# Management_of_Charging_Discharging_Tri-a.net
KiCad netlist of a schematic drawn in Altium Designer
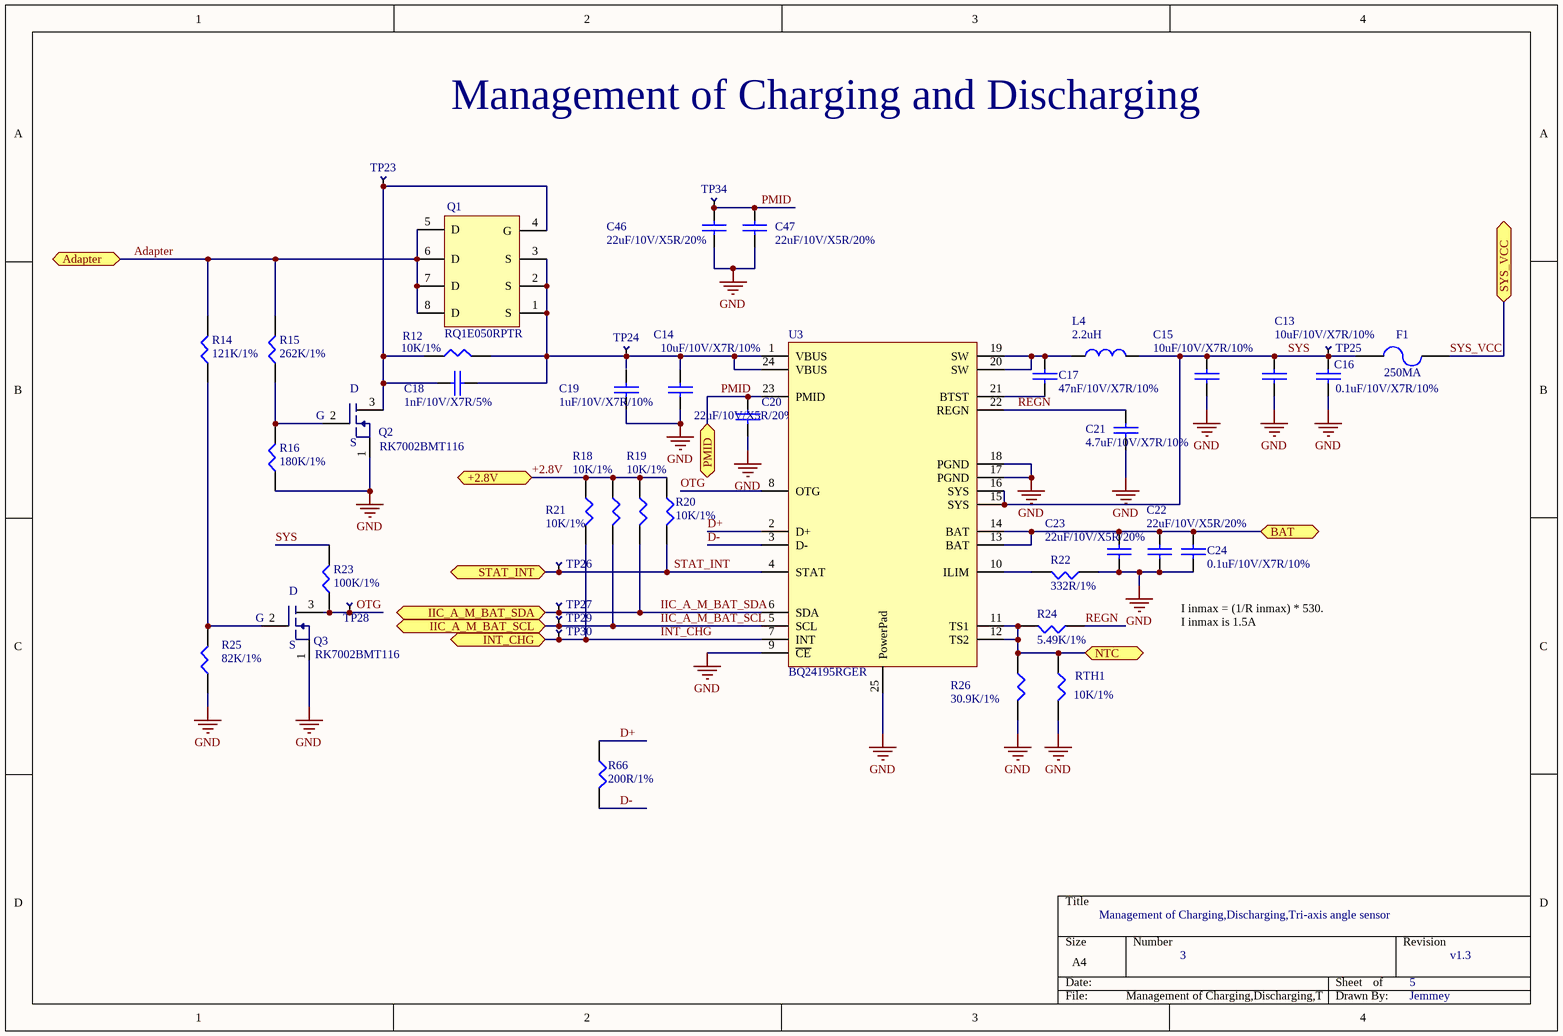
[diagram p0: Management of Charging,Discharging,Tri-axis angle sensor.SchDoc]

(export (version "E")
  (design (tool "Eeschema 10.0.6"))
  (components
    (comp (ref "C13")
      (value "10uF/10V/X7R/10%")
      (footprint "0603C")
      (description "厂家：Murata，型号：GRM188R61A106KE69D")
      (libsource (lib "*") (part "CAP"))
    )
    (comp (ref "C14")
      (value "10uF/10V/X7R/10%")
      (footprint "0603C")
      (description "厂家：Murata，型号：GRM188R61A106KE69D")
      (libsource (lib "*") (part "CAP"))
    )
    (comp (ref "C15")
      (value "10uF/10V/X7R/10%")
      (footprint "0603C")
      (description "厂家：Murata，型号：GRM188R61A106KE69D")
      (libsource (lib "*") (part "CAP"))
    )
    (comp (ref "C16")
      (value "0.1uF/10V/X7R/10%")
      (footprint "0402C")
      (description "厂家：Murata，型号：GRM155R71A104KA01D")
      (libsource (lib "*") (part "CAP"))
    )
    (comp (ref "C17")
      (value "47nF/10V/X7R/10%")
      (footprint "0402C")
      (description "厂家：Murata，型号：GRM155R71H473KE14D")
      (libsource (lib "*") (part "CAP"))
    )
    (comp (ref "C18")
      (value "1nF/10V/X7R/5%")
      (footprint "0402C")
      (description "厂家：Murata，型号：GRM1555C1H102JA01D")
      (libsource (lib "*") (part "CAP"))
    )
    (comp (ref "C19")
      (value "1uF/10V/X7R/10%")
      (footprint "0402C")
      (description "厂家：Murata，型号：GRM155R61C105KA12D")
      (libsource (lib "*") (part "CAP"))
    )
    (comp (ref "C20")
      (value "22uF/10V/X5R/20%")
      (footprint "0603C")
      (description "厂家：Murata，型号：GRM188R61A226ME15D")
      (libsource (lib "*") (part "CAP"))
    )
    (comp (ref "C21")
      (value "4.7uF/10V/X7R/10%")
      (footprint "0603C")
      (description "厂家：Murata，型号：GRM188R61A475KE15D")
      (libsource (lib "*") (part "CAP"))
    )
    (comp (ref "C22")
      (value "22uF/10V/X5R/20%")
      (footprint "0603C")
      (description "厂家：Murata，型号：GRM188R61A226ME15D")
      (libsource (lib "*") (part "CAP"))
    )
    (comp (ref "C23")
      (value "22uF/10V/X5R/20%")
      (footprint "0603C")
      (description "厂家：Murata，型号：GRM188R61A226ME15D")
      (libsource (lib "*") (part "CAP"))
    )
    (comp (ref "C24")
      (value "0.1uF/10V/X7R/10%")
      (footprint "0402C")
      (description "厂家：Murata，型号：GRM155R71A104KA01D")
      (libsource (lib "*") (part "CAP"))
    )
    (comp (ref "C46")
      (value "22uF/10V/X5R/20%")
      (footprint "0603C")
      (description "厂家：Murata，型号：GRM188R61A226ME15D")
      (libsource (lib "*") (part "CAP"))
    )
    (comp (ref "C47")
      (value "22uF/10V/X5R/20%")
      (footprint "0603C")
      (description "厂家：Murata，型号：GRM188R61A226ME15D")
      (libsource (lib "*") (part "CAP"))
    )
    (comp (ref "F1")
      (value "250MA")
      (footprint "1206")
      (description "厂家：万瑞和，型号：WH1206-050")
      (libsource (lib "*") (part "FUSE2"))
    )
    (comp (ref "L4")
      (value "2.2uH")
      (footprint "MMD")
      (description "厂家：Mag，型号：MMD-05AHN2R2M-X2-RM")
      (libsource (lib "Amber") (part "CHOKE"))
    )
    (comp (ref "Q1")
      (value "RQ1E050RPTR")
      (footprint "TSMT8")
      (description "厂家：ROHM，型号：   RQ1E050RPTR")
      (libsource (lib "Amber") (part "RQ1E050RP"))
    )
    (comp (ref "Q2")
      (value "RK7002BMT116")
      (footprint "SOT23")
      (description "厂家：Vishay，型号：RK7002BMT116")
      (libsource (lib "Amber") (part "RK7002BMT116"))
    )
    (comp (ref "Q3")
      (value "RK7002BMT116")
      (footprint "SOT23")
      (description "厂家：Vishay，型号：RK7002BMT116")
      (libsource (lib "Amber") (part "RK7002BMT116"))
    )
    (comp (ref "R12")
      (value "10K/1%")
      (footprint "0402R")
      (description "厂家：Yageo，型号：RC0402FR-0710KL")
      (libsource (lib "*") (part "RES1"))
    )
    (comp (ref "R14")
      (value "121K/1%")
      (footprint "0402R")
      (description "厂家：Yageo，型号：RC0402FR-07121KL")
      (libsource (lib "*") (part "RES1"))
    )
    (comp (ref "R15")
      (value "262K/1%")
      (footprint "0402R")
      (description "厂家：Yageo，型号：RC0402FR-07262KL")
      (libsource (lib "*") (part "RES1"))
    )
    (comp (ref "R16")
      (value "180K/1%")
      (footprint "0402R")
      (description "厂家：Yageo，型号：RC0402FR-07180KL")
      (libsource (lib "*") (part "RES1"))
    )
    (comp (ref "R18")
      (value "10K/1%")
      (footprint "0402R")
      (description "厂家：Yageo，型号：RC0402FR-0710KL")
      (libsource (lib "*") (part "RES1"))
    )
    (comp (ref "R19")
      (value "10K/1%")
      (footprint "0402R")
      (description "厂家：Yageo，型号：RC0402FR-0710KL")
      (libsource (lib "*") (part "RES1"))
    )
    (comp (ref "R20")
      (value "10K/1%")
      (footprint "0402R")
      (description "厂家：Yageo，型号：RC0402FR-0710KL")
      (libsource (lib "*") (part "RES1"))
    )
    (comp (ref "R21")
      (value "10K/1%")
      (footprint "0402R")
      (description "厂家：Yageo，型号：RC0402FR-0710KL")
      (libsource (lib "*") (part "RES1"))
    )
    (comp (ref "R22")
      (value "332R/1%")
      (footprint "0402R")
      (description "厂家：Yageo，型号：RC0402FR-07332RL")
      (libsource (lib "*") (part "RES1"))
    )
    (comp (ref "R23")
      (value "100K/1%")
      (footprint "0402R")
      (description "厂家：Yageo，型号：RC0402FR-07100KL")
      (libsource (lib "*") (part "RES1"))
    )
    (comp (ref "R24")
      (value "5.49K/1%")
      (footprint "0402R")
      (description "厂家：Yageo，型号：RC0402FR-075K49L")
      (libsource (lib "*") (part "RES1"))
    )
    (comp (ref "R25")
      (value "82K/1%")
      (footprint "0402R")
      (description "厂家：Yageo，型号：RC0402FR-0782KL")
      (libsource (lib "*") (part "RES1"))
    )
    (comp (ref "R26")
      (value "30.9K/1%")
      (footprint "0402R")
      (description "厂家：Yageo，型号：RC0402FR-0730K9L")
      (libsource (lib "*") (part "RES1"))
    )
    (comp (ref "R66")
      (value "200R/1%")
      (footprint "0402R")
      (description "厂家：Yageo，型号：RC0402FR-07200RL")
      (libsource (lib "*") (part "RES1"))
    )
    (comp (ref "RTH1")
      (value "10K/1%")
      (footprint "0402R")
      (description "厂家：Yageo，型号：RC0402FR-0710KL")
      (libsource (lib "*") (part "RES1"))
    )
    (comp (ref "TP23")
      (value "TEST")
      (footprint "Test Pad")
      (description "Test Point")
      (libsource (lib "Amber") (part "TEST"))
    )
    (comp (ref "TP24")
      (value "TEST")
      (footprint "Test Pad")
      (description "Test Point")
      (libsource (lib "Amber") (part "TEST"))
    )
    (comp (ref "TP25")
      (value "TEST")
      (footprint "Test Pad")
      (description "Test Point")
      (libsource (lib "Amber") (part "TEST"))
    )
    (comp (ref "TP26")
      (value "TEST")
      (footprint "Test Pad")
      (description "Test Point")
      (libsource (lib "Amber") (part "TEST"))
    )
    (comp (ref "TP27")
      (value "TEST")
      (footprint "Test Pad")
      (description "Test Point")
      (libsource (lib "Amber") (part "TEST"))
    )
    (comp (ref "TP28")
      (value "TEST")
      (footprint "Test Pad")
      (description "Test Point")
      (libsource (lib "Amber") (part "TEST"))
    )
    (comp (ref "TP29")
      (value "TEST")
      (footprint "Test Pad")
      (description "Test Point")
      (libsource (lib "Amber") (part "TEST"))
    )
    (comp (ref "TP30")
      (value "TEST")
      (footprint "Test Pad")
      (description "Test Point")
      (libsource (lib "Amber") (part "TEST"))
    )
    (comp (ref "TP34")
      (value "TEST")
      (footprint "Test Pad")
      (description "Test Point")
      (libsource (lib "Amber") (part "TEST"))
    )
    (comp (ref "U3")
      (value "BQ24195RGER")
      (footprint "RGE")
      (description "厂家：TI，型号：BQ24195RGER")
      (libsource (lib "Amber") (part "BQ24195L"))
    )
  )
  (nets
    (net (code "1") (name "/+2.8V") (class "Default")
      (node (ref "R18") (pin "1") (pinfunction "1_1") (pintype "passive"))
      (node (ref "R19") (pin "1") (pinfunction "1_1") (pintype "passive"))
      (node (ref "R20") (pin "1") (pinfunction "1_1") (pintype "passive"))
      (node (ref "R21") (pin "1") (pinfunction "1_1") (pintype "passive"))
    )
    (net (code "2") (name "/Adapter") (class "Default")
      (node (ref "Q1") (pin "5") (pinfunction "D_5") (pintype "passive"))
      (node (ref "Q1") (pin "6") (pinfunction "D_6") (pintype "passive"))
      (node (ref "Q1") (pin "7") (pinfunction "D_7") (pintype "passive"))
      (node (ref "Q1") (pin "8") (pinfunction "D_8") (pintype "passive"))
      (node (ref "R14") (pin "2") (pinfunction "2_2") (pintype "passive"))
      (node (ref "R15") (pin "2") (pinfunction "2_2") (pintype "passive"))
    )
    (net (code "3") (name "/BAT") (class "Default")
      (node (ref "C22") (pin "1") (pinfunction "1_1") (pintype "passive"))
      (node (ref "C23") (pin "1") (pinfunction "1_1") (pintype "passive"))
      (node (ref "C24") (pin "1") (pinfunction "1_1") (pintype "passive"))
      (node (ref "U3") (pin "13") (pinfunction "BAT_13") (pintype "passive"))
      (node (ref "U3") (pin "14") (pinfunction "BAT_14") (pintype "passive"))
    )
    (net (code "4") (name "/D+") (class "Default")
      (node (ref "R66") (pin "1") (pinfunction "1_1") (pintype "passive"))
      (node (ref "U3") (pin "2") (pinfunction "D+_2") (pintype "passive"))
    )
    (net (code "5") (name "/D-") (class "Default")
      (node (ref "R66") (pin "2") (pinfunction "2_2") (pintype "passive"))
      (node (ref "U3") (pin "3") (pinfunction "D-_3") (pintype "passive"))
    )
    (net (code "6") (name "/IIC_A_M_BAT_SCL") (class "Default")
      (node (ref "R18") (pin "2") (pinfunction "2_2") (pintype "passive"))
      (node (ref "TP29") (pin "1") (pinfunction "1_1") (pintype "passive"))
      (node (ref "U3") (pin "5") (pinfunction "SCL_5") (pintype "passive"))
    )
    (net (code "7") (name "/IIC_A_M_BAT_SDA") (class "Default")
      (node (ref "R19") (pin "2") (pinfunction "2_2") (pintype "passive"))
      (node (ref "TP27") (pin "1") (pinfunction "1_1") (pintype "passive"))
      (node (ref "U3") (pin "6") (pinfunction "SDA_6") (pintype "passive"))
    )
    (net (code "8") (name "/INT_CHG") (class "Default")
      (node (ref "R21") (pin "2") (pinfunction "2_2") (pintype "passive"))
      (node (ref "TP30") (pin "1") (pinfunction "1_1") (pintype "passive"))
      (node (ref "U3") (pin "7") (pinfunction "INT_7") (pintype "passive"))
    )
    (net (code "9") (name "/NTC") (class "Default")
      (node (ref "R24") (pin "2") (pinfunction "2_2") (pintype "passive"))
      (node (ref "R26") (pin "1") (pinfunction "1_1") (pintype "passive"))
      (node (ref "RTH1") (pin "1") (pinfunction "1_1") (pintype "passive"))
      (node (ref "U3") (pin "11") (pinfunction "TS1_11") (pintype "passive"))
      (node (ref "U3") (pin "12") (pinfunction "TS2_12") (pintype "passive"))
    )
    (net (code "10") (name "/OTG") (class "Default")
      (node (ref "Q3") (pin "3") (pinfunction "D_3") (pintype "passive"))
      (node (ref "R23") (pin "1") (pinfunction "1_1") (pintype "passive"))
      (node (ref "TP28") (pin "1") (pinfunction "1_1") (pintype "passive"))
      (node (ref "U3") (pin "8") (pinfunction "OTG_8") (pintype "passive"))
    )
    (net (code "11") (name "/PMID") (class "Default")
      (node (ref "C20") (pin "1") (pinfunction "1_1") (pintype "passive"))
      (node (ref "C46") (pin "1") (pinfunction "1_1") (pintype "passive"))
      (node (ref "C47") (pin "1") (pinfunction "1_1") (pintype "passive"))
      (node (ref "TP34") (pin "1") (pinfunction "1_1") (pintype "passive"))
      (node (ref "U3") (pin "23") (pinfunction "PMID_23") (pintype "passive"))
    )
    (net (code "12") (name "/REGN") (class "Default")
      (node (ref "C21") (pin "1") (pinfunction "1_1") (pintype "passive"))
      (node (ref "R24") (pin "1") (pinfunction "1_1") (pintype "passive"))
      (node (ref "U3") (pin "22") (pinfunction "REGN_22") (pintype "passive"))
    )
    (net (code "13") (name "/STAT_INT") (class "Default")
      (node (ref "R20") (pin "2") (pinfunction "2_2") (pintype "passive"))
      (node (ref "TP26") (pin "1") (pinfunction "1_1") (pintype "passive"))
      (node (ref "U3") (pin "4") (pinfunction "STAT_4") (pintype "passive"))
    )
    (net (code "14") (name "/SYS") (class "Default")
      (node (ref "C13") (pin "1") (pinfunction "1_1") (pintype "passive"))
      (node (ref "C15") (pin "1") (pinfunction "1_1") (pintype "passive"))
      (node (ref "C16") (pin "1") (pinfunction "1_1") (pintype "passive"))
      (node (ref "F1") (pin "2") (pinfunction "2_2") (pintype "passive"))
      (node (ref "L4") (pin "2") (pinfunction "2_2") (pintype "passive"))
      (node (ref "R23") (pin "2") (pinfunction "2_2") (pintype "passive"))
      (node (ref "TP25") (pin "1") (pinfunction "1_1") (pintype "passive"))
      (node (ref "U3") (pin "15") (pinfunction "SYS_15") (pintype "passive"))
      (node (ref "U3") (pin "16") (pinfunction "SYS_16") (pintype "passive"))
    )
    (net (code "15") (name "/SYS_VCC") (class "Default")
      (node (ref "F1") (pin "1") (pinfunction "1_1") (pintype "passive"))
    )
    (net (code "16") (name "GND") (class "Default")
      (node (ref "C13") (pin "2") (pinfunction "2_2") (pintype "passive"))
      (node (ref "C14") (pin "2") (pinfunction "2_2") (pintype "passive"))
      (node (ref "C15") (pin "2") (pinfunction "2_2") (pintype "passive"))
      (node (ref "C16") (pin "2") (pinfunction "2_2") (pintype "passive"))
      (node (ref "C19") (pin "2") (pinfunction "2_2") (pintype "passive"))
      (node (ref "C20") (pin "2") (pinfunction "2_2") (pintype "passive"))
      (node (ref "C21") (pin "2") (pinfunction "2_2") (pintype "passive"))
      (node (ref "C22") (pin "2") (pinfunction "2_2") (pintype "passive"))
      (node (ref "C23") (pin "2") (pinfunction "2_2") (pintype "passive"))
      (node (ref "C24") (pin "2") (pinfunction "2_2") (pintype "passive"))
      (node (ref "C46") (pin "2") (pinfunction "2_2") (pintype "passive"))
      (node (ref "C47") (pin "2") (pinfunction "2_2") (pintype "passive"))
      (node (ref "Q2") (pin "1") (pinfunction "S_1") (pintype "passive"))
      (node (ref "Q3") (pin "1") (pinfunction "S_1") (pintype "passive"))
      (node (ref "R16") (pin "1") (pinfunction "1_1") (pintype "passive"))
      (node (ref "R22") (pin "1") (pinfunction "1_1") (pintype "passive"))
      (node (ref "R25") (pin "1") (pinfunction "1_1") (pintype "passive"))
      (node (ref "R26") (pin "2") (pinfunction "2_2") (pintype "passive"))
      (node (ref "RTH1") (pin "2") (pinfunction "2_2") (pintype "passive"))
      (node (ref "U3") (pin "17") (pinfunction "PGND_17") (pintype "passive"))
      (node (ref "U3") (pin "18") (pinfunction "PGND_18") (pintype "passive"))
      (node (ref "U3") (pin "25") (pinfunction "PowerPad_25") (pintype "passive"))
      (node (ref "U3") (pin "9") (pinfunction "~{CE}_9") (pintype "passive"))
    )
    (net (code "17") (name "Net-(C14-Pad1)") (class "Default")
      (node (ref "C14") (pin "1") (pinfunction "1_1") (pintype "passive"))
      (node (ref "C18") (pin "2") (pinfunction "2_2") (pintype "passive"))
      (node (ref "Q1") (pin "1") (pinfunction "S_1") (pintype "passive"))
      (node (ref "Q1") (pin "2") (pinfunction "S_2") (pintype "passive"))
      (node (ref "Q1") (pin "3") (pinfunction "S_3") (pintype "passive"))
      (node (ref "R12") (pin "2") (pinfunction "2_2") (pintype "passive"))
      (node (ref "TP24") (pin "1") (pinfunction "1_1") (pintype "passive"))
      (node (ref "U3") (pin "1") (pinfunction "VBUS_1") (pintype "passive"))
      (node (ref "U3") (pin "24") (pinfunction "VBUS_24") (pintype "passive"))
    )
    (net (code "18") (name "Net-(C17-Pad1)") (class "Default")
      (node (ref "C17") (pin "1") (pinfunction "1_1") (pintype "passive"))
      (node (ref "L4") (pin "1") (pinfunction "1_1") (pintype "passive"))
      (node (ref "U3") (pin "19") (pinfunction "SW_19") (pintype "passive"))
      (node (ref "U3") (pin "20") (pinfunction "SW_20") (pintype "passive"))
    )
    (net (code "19") (name "Net-(Q1-G)") (class "Default")
      (node (ref "C18") (pin "1") (pinfunction "1_1") (pintype "passive"))
      (node (ref "Q1") (pin "4") (pinfunction "G_4") (pintype "passive"))
      (node (ref "Q2") (pin "3") (pinfunction "D_3") (pintype "passive"))
      (node (ref "R12") (pin "1") (pinfunction "1_1") (pintype "passive"))
      (node (ref "TP23") (pin "1") (pinfunction "1_1") (pintype "passive"))
    )
    (net (code "20") (name "Net-(Q2-G)") (class "Default")
      (node (ref "Q2") (pin "2") (pinfunction "G_2") (pintype "passive"))
      (node (ref "R15") (pin "1") (pinfunction "1_1") (pintype "passive"))
      (node (ref "R16") (pin "2") (pinfunction "2_2") (pintype "passive"))
    )
    (net (code "21") (name "Net-(Q3-G)") (class "Default")
      (node (ref "Q3") (pin "2") (pinfunction "G_2") (pintype "passive"))
      (node (ref "R14") (pin "1") (pinfunction "1_1") (pintype "passive"))
      (node (ref "R25") (pin "2") (pinfunction "2_2") (pintype "passive"))
    )
    (net (code "22") (name "Net-(U3-BTST)") (class "Default")
      (node (ref "C17") (pin "2") (pinfunction "2_2") (pintype "passive"))
      (node (ref "U3") (pin "21") (pinfunction "BTST_21") (pintype "passive"))
    )
    (net (code "23") (name "Net-(U3-ILIM)") (class "Default")
      (node (ref "R22") (pin "2") (pinfunction "2_2") (pintype "passive"))
      (node (ref "U3") (pin "10") (pinfunction "ILIM_10") (pintype "passive"))
    )
    (net (code "24") (name "unconnected-(C19-Pad1)") (class "Default")
      (node (ref "C19") (pin "1") (pinfunction "1_1") (pintype "passive"))
    )
  )
)
